# Motor_Control.net
KiCad netlist of a schematic drawn in Altium Designer
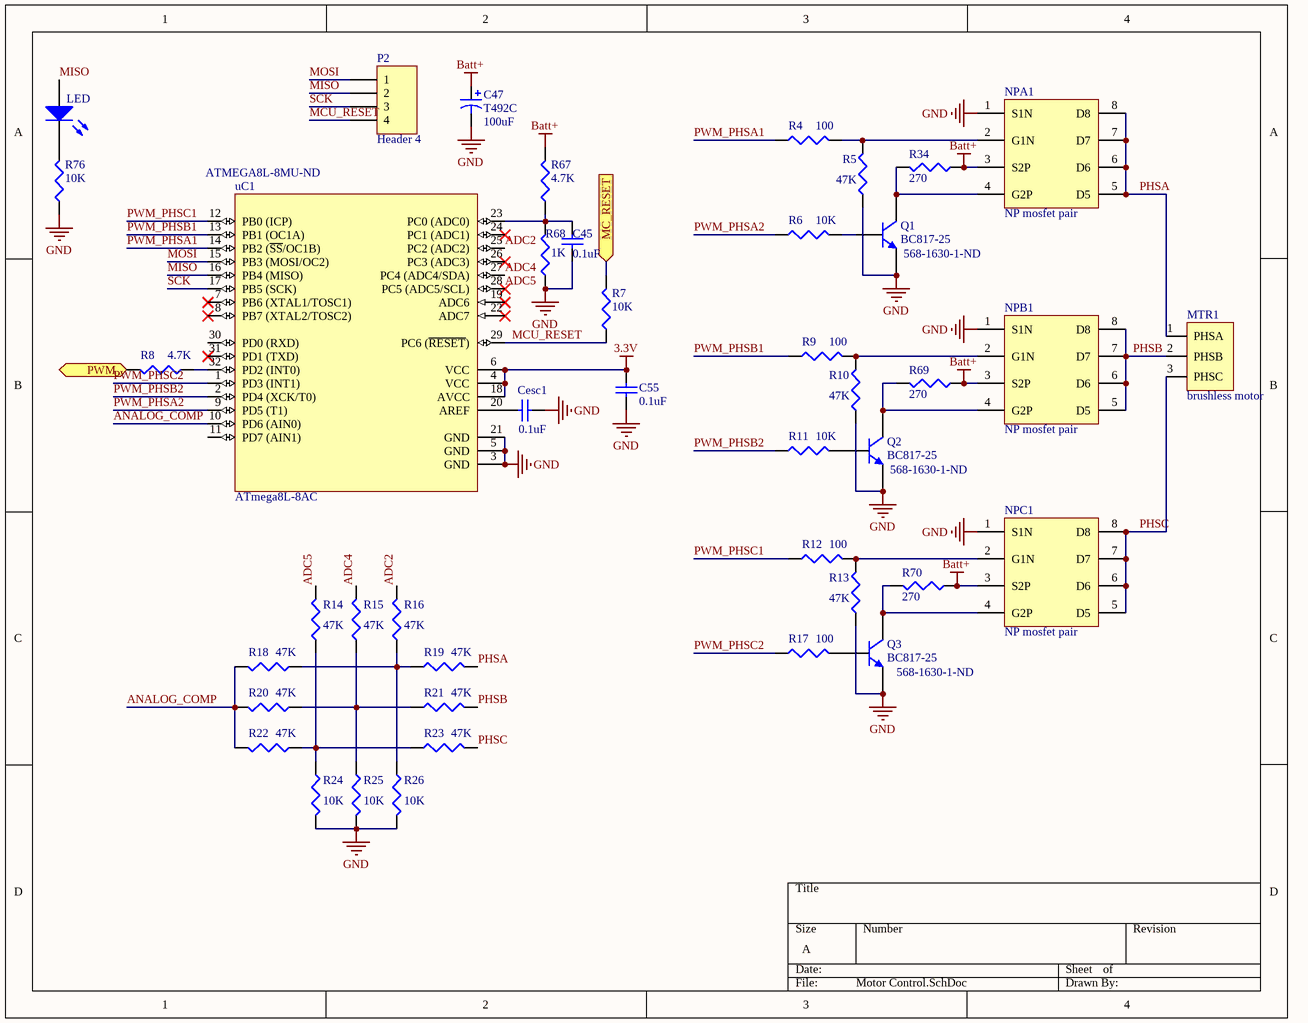
[diagram p0: Motor Control.SchDoc]

(export (version "E")
  (design (tool "Eeschema 10.0.6"))
  (components
    (comp (ref "C45")
      (value "0.1uF")
      (footprint "0603_CAP")
      (description "Capacitor")
      (fields (field (name "Comment") "X7R Cap") (field (name "PUBLISHER") "Altium Limited"))
      (libsource (lib "Miscellaneous Devices") (part "Cap"))
    )
    (comp (ref "C47")
      (value "T492C")
      (footprint "C")
      (description "Solid Tantalum Chip Capacitor, T492 Series - CWR11 Style Per Mil-PRF-55365/8")
      (fields
        (field (name "ALTIUM_VALUE") "100uF")
        (field (name "MANUFACTURER") "Kemet")
        (field (name "MANUFACTURER PART NUMBER") "T491C107K016ZT")
        (field (name "PUBLISHER") "Altium Limited")
      )
      (libsource (lib "KEMET Chip Capacitor") (part "T492C"))
    )
    (comp (ref "C55")
      (value "0.1uF")
      (footprint "0603_CAP")
      (description "Capacitor")
      (fields (field (name "Comment") "X7R Cap") (field (name "PUBLISHER") "Altium Limited"))
      (libsource (lib "Miscellaneous Devices") (part "Cap"))
    )
    (comp (ref "Cesc1")
      (value "0.1uF")
      (footprint "0603_CAP")
      (description "Capacitor")
      (fields (field (name "Comment") "X7R Cap") (field (name "PUBLISHER") "Altium Limited"))
      (libsource (lib "Miscellaneous Devices") (part "Cap"))
    )
    (comp (ref "LED")
      (value "LED0")
      (footprint "0603_RES")
      (description "Typical INFRARED GaAs LED")
      (fields (field (name "PUBLISHER") "Altium Limited"))
      (libsource (lib "Miscellaneous Devices") (part "LED0"))
    )
    (comp (ref "MTR1")
      (value "brushless motor")
      (footprint "Motor Combo")
      (libsource (lib "Components") (part "MOTOR"))
    )
    (comp (ref "NPA1")
      (value "NP mosfet pair")
      (footprint "SOIC127P600-8L")
      (description "AP4503AGM")
      (libsource (lib "Components") (part "AP4503AGM"))
    )
    (comp (ref "NPB1")
      (value "NP mosfet pair")
      (footprint "SOIC127P600-8L")
      (description "AP4503AGM")
      (libsource (lib "Components") (part "AP4503AGM"))
    )
    (comp (ref "NPC1")
      (value "NP mosfet pair")
      (footprint "SOIC127P600-8L")
      (description "AP4503AGM")
      (libsource (lib "Components") (part "AP4503AGM"))
    )
    (comp (ref "P2")
      (value "Header 4")
      (footprint "PRG_HEADER")
      (description "Header, 4-Pin")
      (fields (field (name "PUBLISHER") "Altium Limited"))
      (libsource (lib "Miscellaneous Connectors") (part "Header 4"))
    )
    (comp (ref "Q1")
      (value "BC817-25")
      (footprint "SOT-23")
      (description "NPN General Purpose Amplifier")
      (fields
        (field (name "SUPPLIER PART NUMBER 1") "568-1630-1-ND")
        (field (name "MANUFACTURER") "NXP Semiconductors")
        (field (name "MANUFACTURER PART NUMBER") "BC817-25,215")
        (field (name "PUBLISHER") "Altium Limited")
      )
      (libsource (lib "FSC Discrete BJT") (part "BC817-25"))
    )
    (comp (ref "Q2")
      (value "BC817-25")
      (footprint "SOT-23")
      (description "NPN General Purpose Amplifier")
      (fields
        (field (name "SUPPLIER PART NUMBER 1") "568-1630-1-ND")
        (field (name "MANUFACTURER") "NXP Semiconductors")
        (field (name "MANUFACTURER PART NUMBER") "BC817-25,215")
        (field (name "PUBLISHER") "Altium Limited")
      )
      (libsource (lib "FSC Discrete BJT") (part "BC817-25"))
    )
    (comp (ref "Q3")
      (value "BC817-25")
      (footprint "SOT-23")
      (description "NPN General Purpose Amplifier")
      (fields
        (field (name "SUPPLIER PART NUMBER 1") "568-1630-1-ND")
        (field (name "MANUFACTURER") "NXP Semiconductors")
        (field (name "MANUFACTURER PART NUMBER") "BC817-25,215")
        (field (name "PUBLISHER") "Altium Limited")
      )
      (libsource (lib "FSC Discrete BJT") (part "BC817-25"))
    )
    (comp (ref "R4")
      (value "100")
      (footprint "0603_RES")
      (description "Resistor")
      (fields (field (name "Comment") "Rpull") (field (name "PUBLISHER") "Altium Limited"))
      (libsource (lib "Miscellaneous Devices") (part "Res3"))
    )
    (comp (ref "R5")
      (value "47K")
      (footprint "0603_RES")
      (description "Resistor")
      (fields (field (name "Comment") "Rpull") (field (name "PUBLISHER") "Altium Limited"))
      (libsource (lib "Miscellaneous Devices") (part "Res3"))
    )
    (comp (ref "R6")
      (value "10K")
      (footprint "0603_RES")
      (description "Resistor")
      (fields (field (name "Comment") "Rdrive") (field (name "PUBLISHER") "Altium Limited"))
      (libsource (lib "Miscellaneous Devices") (part "Res3"))
    )
    (comp (ref "R7")
      (value "10K")
      (footprint "0603_RES")
      (description "Resistor")
      (fields (field (name "Comment") "Rpull") (field (name "PUBLISHER") "Altium Limited"))
      (libsource (lib "Miscellaneous Devices") (part "Res3"))
    )
    (comp (ref "R8")
      (value "4.7K")
      (footprint "0603_RES")
      (description "Resistor")
      (fields (field (name "Comment") "Rpull") (field (name "PUBLISHER") "Altium Limited"))
      (libsource (lib "Miscellaneous Devices") (part "Res3"))
    )
    (comp (ref "R9")
      (value "100")
      (footprint "0603_RES")
      (description "Resistor")
      (fields (field (name "Comment") "Rpull") (field (name "PUBLISHER") "Altium Limited"))
      (libsource (lib "Miscellaneous Devices") (part "Res3"))
    )
    (comp (ref "R10")
      (value "47K")
      (footprint "0603_RES")
      (description "Resistor")
      (fields (field (name "Comment") "Rpull") (field (name "PUBLISHER") "Altium Limited"))
      (libsource (lib "Miscellaneous Devices") (part "Res3"))
    )
    (comp (ref "R11")
      (value "10K")
      (footprint "0603_RES")
      (description "Resistor")
      (fields (field (name "Comment") "Rdrive") (field (name "PUBLISHER") "Altium Limited"))
      (libsource (lib "Miscellaneous Devices") (part "Res3"))
    )
    (comp (ref "R12")
      (value "100")
      (footprint "0603_RES")
      (description "Resistor")
      (fields (field (name "Comment") "Rpull") (field (name "PUBLISHER") "Altium Limited"))
      (libsource (lib "Miscellaneous Devices") (part "Res3"))
    )
    (comp (ref "R13")
      (value "47K")
      (footprint "0603_RES")
      (description "Resistor")
      (fields (field (name "Comment") "Rpull") (field (name "PUBLISHER") "Altium Limited"))
      (libsource (lib "Miscellaneous Devices") (part "Res3"))
    )
    (comp (ref "R14")
      (value "47K")
      (footprint "0603_RES")
      (description "Resistor")
      (fields (field (name "Comment") "Rpull") (field (name "PUBLISHER") "Altium Limited"))
      (libsource (lib "Miscellaneous Devices") (part "Res3"))
    )
    (comp (ref "R15")
      (value "47K")
      (footprint "0603_RES")
      (description "Resistor")
      (fields (field (name "Comment") "Rpull") (field (name "PUBLISHER") "Altium Limited"))
      (libsource (lib "Miscellaneous Devices") (part "Res3"))
    )
    (comp (ref "R16")
      (value "47K")
      (footprint "0603_RES")
      (description "Resistor")
      (fields (field (name "Comment") "Rpull") (field (name "PUBLISHER") "Altium Limited"))
      (libsource (lib "Miscellaneous Devices") (part "Res3"))
    )
    (comp (ref "R17")
      (value "100")
      (footprint "0603_RES")
      (description "Resistor")
      (fields (field (name "Comment") "Rpull") (field (name "PUBLISHER") "Altium Limited"))
      (libsource (lib "Miscellaneous Devices") (part "Res3"))
    )
    (comp (ref "R18")
      (value "47K")
      (footprint "0603_RES")
      (description "Resistor")
      (fields (field (name "Comment") "Rpull") (field (name "PUBLISHER") "Altium Limited"))
      (libsource (lib "Miscellaneous Devices") (part "Res3"))
    )
    (comp (ref "R19")
      (value "47K")
      (footprint "0603_RES")
      (description "Resistor")
      (fields (field (name "Comment") "Rpull") (field (name "PUBLISHER") "Altium Limited"))
      (libsource (lib "Miscellaneous Devices") (part "Res3"))
    )
    (comp (ref "R20")
      (value "47K")
      (footprint "0603_RES")
      (description "Resistor")
      (fields (field (name "Comment") "Rpull") (field (name "PUBLISHER") "Altium Limited"))
      (libsource (lib "Miscellaneous Devices") (part "Res3"))
    )
    (comp (ref "R21")
      (value "47K")
      (footprint "0603_RES")
      (description "Resistor")
      (fields (field (name "Comment") "Rpull") (field (name "PUBLISHER") "Altium Limited"))
      (libsource (lib "Miscellaneous Devices") (part "Res3"))
    )
    (comp (ref "R22")
      (value "47K")
      (footprint "0603_RES")
      (description "Resistor")
      (fields (field (name "Comment") "Rpull") (field (name "PUBLISHER") "Altium Limited"))
      (libsource (lib "Miscellaneous Devices") (part "Res3"))
    )
    (comp (ref "R23")
      (value "47K")
      (footprint "0603_RES")
      (description "Resistor")
      (fields (field (name "Comment") "Rpull") (field (name "PUBLISHER") "Altium Limited"))
      (libsource (lib "Miscellaneous Devices") (part "Res3"))
    )
    (comp (ref "R24")
      (value "10K")
      (footprint "0603_RES")
      (description "Resistor")
      (fields (field (name "Comment") "Rpull") (field (name "PUBLISHER") "Altium Limited"))
      (libsource (lib "Miscellaneous Devices") (part "Res3"))
    )
    (comp (ref "R25")
      (value "10K")
      (footprint "0603_RES")
      (description "Resistor")
      (fields (field (name "Comment") "Rpull") (field (name "PUBLISHER") "Altium Limited"))
      (libsource (lib "Miscellaneous Devices") (part "Res3"))
    )
    (comp (ref "R26")
      (value "10K")
      (footprint "0603_RES")
      (description "Resistor")
      (fields (field (name "Comment") "Rpull") (field (name "PUBLISHER") "Altium Limited"))
      (libsource (lib "Miscellaneous Devices") (part "Res3"))
    )
    (comp (ref "R34")
      (value "270")
      (footprint "0603_RES")
      (description "Resistor")
      (fields (field (name "Comment") "Rpull") (field (name "PUBLISHER") "Altium Limited"))
      (libsource (lib "Miscellaneous Devices") (part "Res3"))
    )
    (comp (ref "R67")
      (value "4.7K")
      (footprint "0603_RES")
      (description "Resistor")
      (fields (field (name "Comment") "Rpull") (field (name "PUBLISHER") "Altium Limited"))
      (libsource (lib "Miscellaneous Devices") (part "Res3"))
    )
    (comp (ref "R68")
      (value "1K")
      (footprint "0603_RES")
      (description "Resistor")
      (fields (field (name "Comment") "Rpull") (field (name "PUBLISHER") "Altium Limited"))
      (libsource (lib "Miscellaneous Devices") (part "Res3"))
    )
    (comp (ref "R69")
      (value "270")
      (footprint "0603_RES")
      (description "Resistor")
      (fields (field (name "Comment") "Rpull") (field (name "PUBLISHER") "Altium Limited"))
      (libsource (lib "Miscellaneous Devices") (part "Res3"))
    )
    (comp (ref "R70")
      (value "270")
      (footprint "0603_RES")
      (description "Resistor")
      (fields (field (name "Comment") "Rpull") (field (name "PUBLISHER") "Altium Limited"))
      (libsource (lib "Miscellaneous Devices") (part "Res3"))
    )
    (comp (ref "R76")
      (value "10K")
      (footprint "0603_RES")
      (description "Resistor")
      (fields (field (name "Comment") "Rpull") (field (name "PUBLISHER") "Altium Limited"))
      (libsource (lib "Miscellaneous Devices") (part "Res3"))
    )
    (comp (ref "uC1")
      (value "ATmega8L-8AC")
      (footprint "32A_N")
      (description "8-Bit AVR Microcontroller with 8K Bytes of In-System Programmable Flash Memory")
      (fields
        (field (name "MANUFACTURER") "Atmel")
        (field (name "MANUFACTURER PART NUMBER") "ATMEGA8L-8AU")
        (field (name "SUPPLIER PART NUMBER 1") "ATMEGA8L-8MU-ND")
        (field (name "PUBLISHER") "Altium Limited")
      )
      (libsource (lib "Atmel Microcontroller 8-Bit AVR") (part "ATmega8L-8AC"))
    )
  )
  (nets
    (net (code "1") (name "/ADC2") (class "Default")
      (node (ref "R16") (pin "2") (pinfunction "2_2") (pintype "passive"))
      (node (ref "uC1") (pin "25") (pinfunction "PC2_(ADC2)_25") (pintype "bidirectional"))
    )
    (net (code "2") (name "/ADC4") (class "Default")
      (node (ref "R15") (pin "2") (pinfunction "2_2") (pintype "passive"))
      (node (ref "uC1") (pin "27") (pinfunction "PC4_(ADC4/SDA)_27") (pintype "bidirectional"))
    )
    (net (code "3") (name "/ADC5") (class "Default")
      (node (ref "R14") (pin "2") (pinfunction "2_2") (pintype "passive"))
      (node (ref "uC1") (pin "28") (pinfunction "PC5_(ADC5/SCL)_28") (pintype "bidirectional"))
    )
    (net (code "4") (name "/ANALOG_COMP") (class "Default")
      (node (ref "R18") (pin "2") (pinfunction "2_2") (pintype "passive"))
      (node (ref "R20") (pin "2") (pinfunction "2_2") (pintype "passive"))
      (node (ref "R22") (pin "2") (pinfunction "2_2") (pintype "passive"))
      (node (ref "uC1") (pin "10") (pinfunction "PD6_(AIN0)_10") (pintype "bidirectional"))
    )
    (net (code "5") (name "/MCU_RESET") (class "Default")
      (node (ref "P2") (pin "4") (pinfunction "4_4") (pintype "passive"))
      (node (ref "R7") (pin "1") (pinfunction "1_1") (pintype "passive"))
      (node (ref "uC1") (pin "29") (pinfunction "PC6_(~{RESET})_29") (pintype "bidirectional"))
    )
    (net (code "6") (name "/MC_RESET") (class "Default")
      (node (ref "R7") (pin "2") (pinfunction "2_2") (pintype "passive"))
    )
    (net (code "7") (name "/MISO") (class "Default")
      (node (ref "LED") (pin "1") (pinfunction "A_1") (pintype "passive"))
      (node (ref "P2") (pin "2") (pinfunction "2_2") (pintype "passive"))
      (node (ref "uC1") (pin "16") (pinfunction "PB4_(MISO)_16") (pintype "bidirectional"))
    )
    (net (code "8") (name "/MOSI") (class "Default")
      (node (ref "P2") (pin "1") (pinfunction "1_1") (pintype "passive"))
      (node (ref "uC1") (pin "15") (pinfunction "PB3_(MOSI/OC2)_15") (pintype "bidirectional"))
    )
    (net (code "9") (name "/PHSA") (class "Default")
      (node (ref "MTR1") (pin "1") (pinfunction "PHSA_1") (pintype "passive"))
      (node (ref "NPA1") (pin "5") (pinfunction "D5_5") (pintype "passive"))
      (node (ref "NPA1") (pin "6") (pinfunction "D6_6") (pintype "passive"))
      (node (ref "NPA1") (pin "7") (pinfunction "D7_7") (pintype "passive"))
      (node (ref "NPA1") (pin "8") (pinfunction "D8_8") (pintype "passive"))
      (node (ref "R19") (pin "2") (pinfunction "2_2") (pintype "passive"))
    )
    (net (code "10") (name "/PHSB") (class "Default")
      (node (ref "MTR1") (pin "2") (pinfunction "PHSB_2") (pintype "passive"))
      (node (ref "NPB1") (pin "5") (pinfunction "D5_5") (pintype "passive"))
      (node (ref "NPB1") (pin "6") (pinfunction "D6_6") (pintype "passive"))
      (node (ref "NPB1") (pin "7") (pinfunction "D7_7") (pintype "passive"))
      (node (ref "NPB1") (pin "8") (pinfunction "D8_8") (pintype "passive"))
      (node (ref "R21") (pin "2") (pinfunction "2_2") (pintype "passive"))
    )
    (net (code "11") (name "/PHSC") (class "Default")
      (node (ref "MTR1") (pin "3") (pinfunction "PHSC_3") (pintype "passive"))
      (node (ref "NPC1") (pin "5") (pinfunction "D5_5") (pintype "passive"))
      (node (ref "NPC1") (pin "6") (pinfunction "D6_6") (pintype "passive"))
      (node (ref "NPC1") (pin "7") (pinfunction "D7_7") (pintype "passive"))
      (node (ref "NPC1") (pin "8") (pinfunction "D8_8") (pintype "passive"))
      (node (ref "R23") (pin "2") (pinfunction "2_2") (pintype "passive"))
    )
    (net (code "12") (name "/PWM") (class "Default")
      (node (ref "R8") (pin "2") (pinfunction "2_2") (pintype "passive"))
    )
    (net (code "13") (name "/PWM_PHSA1") (class "Default")
      (node (ref "R4") (pin "1") (pinfunction "1_1") (pintype "passive"))
      (node (ref "uC1") (pin "14") (pinfunction "PB2_(~{SS}/OC1B)_14") (pintype "bidirectional"))
    )
    (net (code "14") (name "/PWM_PHSA2") (class "Default")
      (node (ref "R6") (pin "1") (pinfunction "1_1") (pintype "passive"))
      (node (ref "uC1") (pin "9") (pinfunction "PD5_(T1)_9") (pintype "bidirectional"))
    )
    (net (code "15") (name "/PWM_PHSB1") (class "Default")
      (node (ref "R9") (pin "1") (pinfunction "1_1") (pintype "passive"))
      (node (ref "uC1") (pin "13") (pinfunction "PB1_(OC1A)_13") (pintype "bidirectional"))
    )
    (net (code "16") (name "/PWM_PHSB2") (class "Default")
      (node (ref "R11") (pin "1") (pinfunction "1_1") (pintype "passive"))
      (node (ref "uC1") (pin "2") (pinfunction "PD4_(XCK/T0)_2") (pintype "bidirectional"))
    )
    (net (code "17") (name "/PWM_PHSC1") (class "Default")
      (node (ref "R12") (pin "1") (pinfunction "1_1") (pintype "passive"))
      (node (ref "uC1") (pin "12") (pinfunction "PB0_(ICP)_12") (pintype "bidirectional"))
    )
    (net (code "18") (name "/PWM_PHSC2") (class "Default")
      (node (ref "R17") (pin "1") (pinfunction "1_1") (pintype "passive"))
      (node (ref "uC1") (pin "1") (pinfunction "PD3_(INT1)_1") (pintype "bidirectional"))
    )
    (net (code "19") (name "/SCK") (class "Default")
      (node (ref "P2") (pin "3") (pinfunction "3_3") (pintype "passive"))
      (node (ref "uC1") (pin "17") (pinfunction "PB5_(SCK)_17") (pintype "bidirectional"))
    )
    (net (code "20") (name "3.3V") (class "Default")
      (node (ref "C55") (pin "1") (pinfunction "1_1") (pintype "passive"))
      (node (ref "uC1") (pin "18") (pinfunction "AVCC_18") (pintype "power_in"))
      (node (ref "uC1") (pin "4") (pinfunction "VCC_4") (pintype "power_in"))
      (node (ref "uC1") (pin "6") (pinfunction "VCC_6") (pintype "power_in"))
    )
    (net (code "21") (name "Batt+") (class "Default")
      (node (ref "C47") (pin "1") (pinfunction "1_1") (pintype "passive"))
      (node (ref "NPA1") (pin "3") (pinfunction "S2P_3") (pintype "passive"))
      (node (ref "NPB1") (pin "3") (pinfunction "S2P_3") (pintype "passive"))
      (node (ref "NPC1") (pin "3") (pinfunction "S2P_3") (pintype "passive"))
      (node (ref "R34") (pin "1") (pinfunction "1_1") (pintype "passive"))
      (node (ref "R67") (pin "2") (pinfunction "2_2") (pintype "passive"))
      (node (ref "R69") (pin "1") (pinfunction "1_1") (pintype "passive"))
      (node (ref "R70") (pin "1") (pinfunction "1_1") (pintype "passive"))
    )
    (net (code "22") (name "GND") (class "Default")
      (node (ref "C45") (pin "2") (pinfunction "2_2") (pintype "passive"))
      (node (ref "C47") (pin "2") (pinfunction "2_2") (pintype "passive"))
      (node (ref "C55") (pin "2") (pinfunction "2_2") (pintype "passive"))
      (node (ref "Cesc1") (pin "1") (pinfunction "1_1") (pintype "passive"))
      (node (ref "NPA1") (pin "1") (pinfunction "S1N_1") (pintype "passive"))
      (node (ref "NPB1") (pin "1") (pinfunction "S1N_1") (pintype "passive"))
      (node (ref "NPC1") (pin "1") (pinfunction "S1N_1") (pintype "passive"))
      (node (ref "Q1") (pin "2") (pinfunction "E_2") (pintype "passive"))
      (node (ref "Q2") (pin "2") (pinfunction "E_2") (pintype "passive"))
      (node (ref "Q3") (pin "2") (pinfunction "E_2") (pintype "passive"))
      (node (ref "R10") (pin "1") (pinfunction "1_1") (pintype "passive"))
      (node (ref "R13") (pin "1") (pinfunction "1_1") (pintype "passive"))
      (node (ref "R24") (pin "2") (pinfunction "2_2") (pintype "passive"))
      (node (ref "R25") (pin "2") (pinfunction "2_2") (pintype "passive"))
      (node (ref "R26") (pin "2") (pinfunction "2_2") (pintype "passive"))
      (node (ref "R5") (pin "1") (pinfunction "1_1") (pintype "passive"))
      (node (ref "R68") (pin "1") (pinfunction "1_1") (pintype "passive"))
      (node (ref "R76") (pin "1") (pinfunction "1_1") (pintype "passive"))
      (node (ref "uC1") (pin "21") (pinfunction "GND_21") (pintype "power_in"))
      (node (ref "uC1") (pin "3") (pinfunction "GND_3") (pintype "power_in"))
      (node (ref "uC1") (pin "5") (pinfunction "GND_5") (pintype "power_in"))
    )
    (net (code "23") (name "Net-(LED-K)") (class "Default")
      (node (ref "LED") (pin "2") (pinfunction "K_2") (pintype "passive"))
      (node (ref "R76") (pin "2") (pinfunction "2_2") (pintype "passive"))
    )
    (net (code "24") (name "Net-(NPA1-G1N)") (class "Default")
      (node (ref "NPA1") (pin "2") (pinfunction "G1N_2") (pintype "passive"))
      (node (ref "R4") (pin "2") (pinfunction "2_2") (pintype "passive"))
      (node (ref "R5") (pin "2") (pinfunction "2_2") (pintype "passive"))
    )
    (net (code "25") (name "Net-(NPA1-G2P)") (class "Default")
      (node (ref "NPA1") (pin "4") (pinfunction "G2P_4") (pintype "passive"))
      (node (ref "Q1") (pin "3") (pinfunction "C_3") (pintype "passive"))
      (node (ref "R34") (pin "2") (pinfunction "2_2") (pintype "passive"))
    )
    (net (code "26") (name "Net-(NPB1-G1N)") (class "Default")
      (node (ref "NPB1") (pin "2") (pinfunction "G1N_2") (pintype "passive"))
      (node (ref "R10") (pin "2") (pinfunction "2_2") (pintype "passive"))
      (node (ref "R9") (pin "2") (pinfunction "2_2") (pintype "passive"))
    )
    (net (code "27") (name "Net-(NPB1-G2P)") (class "Default")
      (node (ref "NPB1") (pin "4") (pinfunction "G2P_4") (pintype "passive"))
      (node (ref "Q2") (pin "3") (pinfunction "C_3") (pintype "passive"))
      (node (ref "R69") (pin "2") (pinfunction "2_2") (pintype "passive"))
    )
    (net (code "28") (name "Net-(NPC1-G1N)") (class "Default")
      (node (ref "NPC1") (pin "2") (pinfunction "G1N_2") (pintype "passive"))
      (node (ref "R12") (pin "2") (pinfunction "2_2") (pintype "passive"))
      (node (ref "R13") (pin "2") (pinfunction "2_2") (pintype "passive"))
    )
    (net (code "29") (name "Net-(NPC1-G2P)") (class "Default")
      (node (ref "NPC1") (pin "4") (pinfunction "G2P_4") (pintype "passive"))
      (node (ref "Q3") (pin "3") (pinfunction "C_3") (pintype "passive"))
      (node (ref "R70") (pin "2") (pinfunction "2_2") (pintype "passive"))
    )
    (net (code "30") (name "Net-(Q1-B)") (class "Default")
      (node (ref "Q1") (pin "1") (pinfunction "B_1") (pintype "passive"))
      (node (ref "R6") (pin "2") (pinfunction "2_2") (pintype "passive"))
    )
    (net (code "31") (name "Net-(Q2-B)") (class "Default")
      (node (ref "Q2") (pin "1") (pinfunction "B_1") (pintype "passive"))
      (node (ref "R11") (pin "2") (pinfunction "2_2") (pintype "passive"))
    )
    (net (code "32") (name "Net-(Q3-B)") (class "Default")
      (node (ref "Q3") (pin "1") (pinfunction "B_1") (pintype "passive"))
      (node (ref "R17") (pin "2") (pinfunction "2_2") (pintype "passive"))
    )
    (net (code "33") (name "Net-(R14-Pad1)") (class "Default")
      (node (ref "R14") (pin "1") (pinfunction "1_1") (pintype "passive"))
      (node (ref "R22") (pin "1") (pinfunction "1_1") (pintype "passive"))
      (node (ref "R23") (pin "1") (pinfunction "1_1") (pintype "passive"))
      (node (ref "R24") (pin "1") (pinfunction "1_1") (pintype "passive"))
    )
    (net (code "34") (name "Net-(R15-Pad1)") (class "Default")
      (node (ref "R15") (pin "1") (pinfunction "1_1") (pintype "passive"))
      (node (ref "R20") (pin "1") (pinfunction "1_1") (pintype "passive"))
      (node (ref "R21") (pin "1") (pinfunction "1_1") (pintype "passive"))
      (node (ref "R25") (pin "1") (pinfunction "1_1") (pintype "passive"))
    )
    (net (code "35") (name "Net-(R16-Pad1)") (class "Default")
      (node (ref "R16") (pin "1") (pinfunction "1_1") (pintype "passive"))
      (node (ref "R18") (pin "1") (pinfunction "1_1") (pintype "passive"))
      (node (ref "R19") (pin "1") (pinfunction "1_1") (pintype "passive"))
      (node (ref "R26") (pin "1") (pinfunction "1_1") (pintype "passive"))
    )
    (net (code "36") (name "Net-(uC1-AREF)") (class "Default")
      (node (ref "Cesc1") (pin "2") (pinfunction "2_2") (pintype "passive"))
      (node (ref "uC1") (pin "20") (pinfunction "AREF_20") (pintype "passive"))
    )
    (net (code "37") (name "Net-(uC1-PC0_(ADC0))") (class "Default")
      (node (ref "C45") (pin "1") (pinfunction "1_1") (pintype "passive"))
      (node (ref "R67") (pin "1") (pinfunction "1_1") (pintype "passive"))
      (node (ref "R68") (pin "2") (pinfunction "2_2") (pintype "passive"))
      (node (ref "uC1") (pin "23") (pinfunction "PC0_(ADC0)_23") (pintype "bidirectional"))
    )
    (net (code "38") (name "Net-(uC1-PD2_(INT0))") (class "Default")
      (node (ref "R8") (pin "1") (pinfunction "1_1") (pintype "passive"))
      (node (ref "uC1") (pin "32") (pinfunction "PD2_(INT0)_32") (pintype "bidirectional"))
    )
    (net (code "39") (name "unconnected-(uC1-ADC6-Pad19)") (class "Default")
      (node (ref "uC1") (pin "19") (pinfunction "ADC6_19") (pintype "input+no_connect"))
    )
    (net (code "40") (name "unconnected-(uC1-ADC7-Pad22)") (class "Default")
      (node (ref "uC1") (pin "22") (pinfunction "ADC7_22") (pintype "input+no_connect"))
    )
    (net (code "41") (name "unconnected-(uC1-PB6_(XTAL1{slash}TOSC1)-Pad7)") (class "Default")
      (node (ref "uC1") (pin "7") (pinfunction "PB6_(XTAL1/TOSC1)_7") (pintype "bidirectional+no_connect"))
    )
    (net (code "42") (name "unconnected-(uC1-PB7_(XTAL2{slash}TOSC2)-Pad8)") (class "Default")
      (node (ref "uC1") (pin "8") (pinfunction "PB7_(XTAL2/TOSC2)_8") (pintype "bidirectional+no_connect"))
    )
    (net (code "43") (name "unconnected-(uC1-PC1_(ADC1)-Pad24)") (class "Default")
      (node (ref "uC1") (pin "24") (pinfunction "PC1_(ADC1)_24") (pintype "bidirectional+no_connect"))
    )
    (net (code "44") (name "unconnected-(uC1-PC3_(ADC3)-Pad26)") (class "Default")
      (node (ref "uC1") (pin "26") (pinfunction "PC3_(ADC3)_26") (pintype "bidirectional+no_connect"))
    )
    (net (code "45") (name "unconnected-(uC1-PD0_(RXD)-Pad30)") (class "Default")
      (node (ref "uC1") (pin "30") (pinfunction "PD0_(RXD)_30") (pintype "bidirectional"))
    )
    (net (code "46") (name "unconnected-(uC1-PD1_(TXD)-Pad31)") (class "Default")
      (node (ref "uC1") (pin "31") (pinfunction "PD1_(TXD)_31") (pintype "bidirectional+no_connect"))
    )
    (net (code "47") (name "unconnected-(uC1-PD7_(AIN1)-Pad11)") (class "Default")
      (node (ref "uC1") (pin "11") (pinfunction "PD7_(AIN1)_11") (pintype "bidirectional"))
    )
  )
)
